# LCboardRev3.net
KiCad netlist of a schematic drawn in Altium Designer
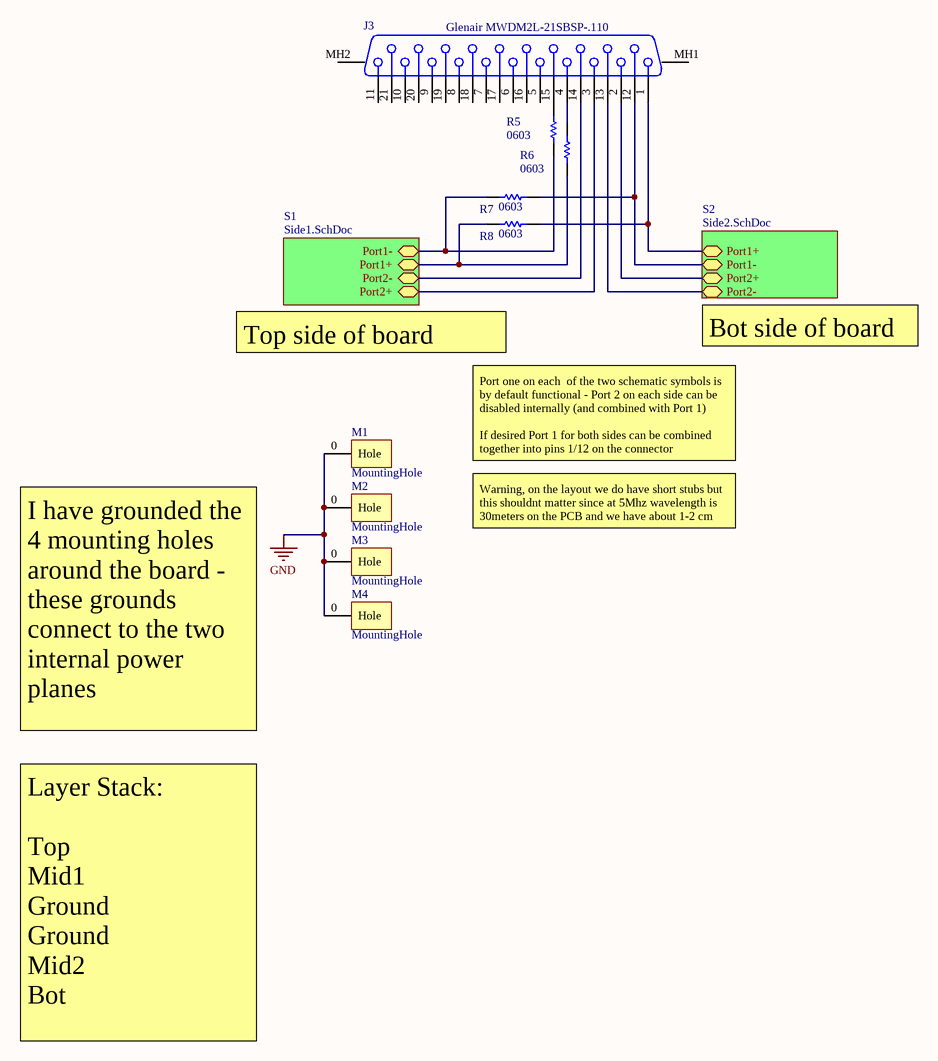
[diagram p0: LCboardRev3.SchDoc]

(export (version "E")
  (design (tool "Eeschema 10.0.6"))
  (components
    (comp (ref "J3")
      (value "Glenair MWDM2L-21SBSP-.110")
      (footprint "MicroD21Glenair-Vert2row")
      (description "GlenairMicroDsub21 -2 row")
      (libsource (lib "LCboardPCB") (part "GlenairMicroDsub21 -2 row"))
    )
    (comp (ref "M1")
      (value "MountingHole")
      (footprint "MountingHole")
      (libsource (lib "LCboardPCB") (part "MountingHole"))
    )
    (comp (ref "M2")
      (value "MountingHole")
      (footprint "MountingHole")
      (libsource (lib "LCboardPCB") (part "MountingHole"))
    )
    (comp (ref "M3")
      (value "MountingHole")
      (footprint "MountingHole")
      (libsource (lib "LCboardPCB") (part "MountingHole"))
    )
    (comp (ref "M4")
      (value "MountingHole")
      (footprint "MountingHole")
      (libsource (lib "LCboardPCB") (part "MountingHole"))
    )
    (comp (ref "R5")
      (value "0603")
      (footprint "0603")
      (description "RES 1 OHM 1/10W 1% 0603 SMD")
      (libsource (lib "LCboardPCB") (part "Res0603"))
    )
    (comp (ref "R6")
      (value "0603")
      (footprint "0603")
      (description "RES 1 OHM 1/10W 1% 0603 SMD")
      (libsource (lib "LCboardPCB") (part "Res0603"))
    )
    (comp (ref "R7")
      (value "0603")
      (footprint "0603")
      (description "RES 1 OHM 1/10W 1% 0603 SMD")
      (libsource (lib "LCboardPCB") (part "Res0603"))
    )
    (comp (ref "R8")
      (value "0603")
      (footprint "0603")
      (description "RES 1 OHM 1/10W 1% 0603 SMD")
      (libsource (lib "LCboardPCB") (part "Res0603"))
    )
  )
  (nets
    (net (code "1") (name "/Port1+") (class "Default")
      (node (ref "J3") (pin "1") (pinfunction "1_1") (pintype "passive"))
      (node (ref "R8") (pin "2") (pinfunction "2_2") (pintype "passive"))
    )
    (net (code "2") (name "/Port1+_1") (class "Default")
      (node (ref "R6") (pin "1") (pinfunction "1_1") (pintype "passive"))
      (node (ref "R8") (pin "1") (pinfunction "1_1") (pintype "passive"))
    )
    (net (code "3") (name "/Port1-") (class "Default")
      (node (ref "J3") (pin "12") (pinfunction "12_12") (pintype "passive"))
      (node (ref "R7") (pin "2") (pinfunction "2_2") (pintype "passive"))
    )
    (net (code "4") (name "/Port1-_1") (class "Default")
      (node (ref "R5") (pin "1") (pinfunction "1_1") (pintype "passive"))
      (node (ref "R7") (pin "1") (pinfunction "1_1") (pintype "passive"))
    )
    (net (code "5") (name "/Port2+") (class "Default")
      (node (ref "J3") (pin "2") (pinfunction "2_2") (pintype "passive"))
    )
    (net (code "6") (name "/Port2+_1") (class "Default")
      (node (ref "J3") (pin "3") (pinfunction "3_3") (pintype "passive"))
    )
    (net (code "7") (name "/Port2-") (class "Default")
      (node (ref "J3") (pin "13") (pinfunction "13_13") (pintype "passive"))
    )
    (net (code "8") (name "/Port2-_1") (class "Default")
      (node (ref "J3") (pin "14") (pinfunction "14_14") (pintype "passive"))
    )
    (net (code "9") (name "GND") (class "Default")
      (node (ref "M1") (pin "0") (pinfunction "Hole_0") (pintype "passive"))
      (node (ref "M2") (pin "0") (pinfunction "Hole_0") (pintype "passive"))
      (node (ref "M3") (pin "0") (pinfunction "Hole_0") (pintype "passive"))
      (node (ref "M4") (pin "0") (pinfunction "Hole_0") (pintype "passive"))
    )
    (net (code "10") (name "Net-(J3-Pad4)") (class "Default")
      (node (ref "J3") (pin "4") (pinfunction "4_4") (pintype "passive"))
      (node (ref "R6") (pin "2") (pinfunction "2_2") (pintype "passive"))
    )
    (net (code "11") (name "Net-(J3-Pad15)") (class "Default")
      (node (ref "J3") (pin "15") (pinfunction "15_15") (pintype "passive"))
      (node (ref "R5") (pin "2") (pinfunction "2_2") (pintype "passive"))
    )
    (net (code "12") (name "unconnected-(J3-Pad5)") (class "Default")
      (node (ref "J3") (pin "5") (pinfunction "5_5") (pintype "passive"))
    )
    (net (code "13") (name "unconnected-(J3-Pad6)") (class "Default")
      (node (ref "J3") (pin "6") (pinfunction "6_6") (pintype "passive"))
    )
    (net (code "14") (name "unconnected-(J3-Pad7)") (class "Default")
      (node (ref "J3") (pin "7") (pinfunction "7_7") (pintype "passive"))
    )
    (net (code "15") (name "unconnected-(J3-Pad8)") (class "Default")
      (node (ref "J3") (pin "8") (pinfunction "8_8") (pintype "passive"))
    )
    (net (code "16") (name "unconnected-(J3-Pad9)") (class "Default")
      (node (ref "J3") (pin "9") (pinfunction "9_9") (pintype "passive"))
    )
    (net (code "17") (name "unconnected-(J3-Pad10)") (class "Default")
      (node (ref "J3") (pin "10") (pinfunction "10_10") (pintype "passive"))
    )
    (net (code "18") (name "unconnected-(J3-Pad11)") (class "Default")
      (node (ref "J3") (pin "11") (pinfunction "11_11") (pintype "passive"))
    )
    (net (code "19") (name "unconnected-(J3-Pad16)") (class "Default")
      (node (ref "J3") (pin "16") (pinfunction "16_16") (pintype "passive"))
    )
    (net (code "20") (name "unconnected-(J3-Pad17)") (class "Default")
      (node (ref "J3") (pin "17") (pinfunction "17_17") (pintype "passive"))
    )
    (net (code "21") (name "unconnected-(J3-Pad18)") (class "Default")
      (node (ref "J3") (pin "18") (pinfunction "18_18") (pintype "passive"))
    )
    (net (code "22") (name "unconnected-(J3-Pad19)") (class "Default")
      (node (ref "J3") (pin "19") (pinfunction "19_19") (pintype "passive"))
    )
    (net (code "23") (name "unconnected-(J3-Pad20)") (class "Default")
      (node (ref "J3") (pin "20") (pinfunction "20_20") (pintype "passive"))
    )
    (net (code "24") (name "unconnected-(J3-Pad21)") (class "Default")
      (node (ref "J3") (pin "21") (pinfunction "21_21") (pintype "passive"))
    )
    (net (code "25") (name "unconnected-(J3-PadMH1)") (class "Default")
      (node (ref "J3") (pin "MH1") (pinfunction "MH1_MH1") (pintype "passive"))
    )
    (net (code "26") (name "unconnected-(J3-PadMH2)") (class "Default")
      (node (ref "J3") (pin "MH2") (pinfunction "MH2_MH2") (pintype "passive"))
    )
  )
)
